# 06_-_IO_Ports.net
KiCad netlist of a schematic drawn in Altium Designer
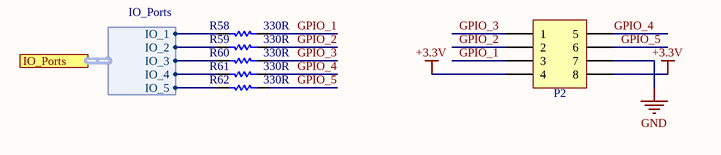
[diagram p0: [06] - IO_Ports.SchDoc]

(export (version "E")
  (design (tool "Eeschema 10.0.6"))
  (components
    (comp (ref "P2")
      (value "Header 4X2A")
      (footprint "HDR2X4_CEN")
      (description "Header, 4-Pin, Dual row")
      (fields (field (name "PUBLISHER") "Altium Limited"))
      (libsource (lib "Miscellaneous Connectors") (part "Header 4X2A"))
    )
    (comp (ref "R58")
      (value "Res1")
      (footprint "Res-0603")
      (description "Chip Resistor")
      (fields
        (field (name "MANUFACTURER") "Panasonic")
        (field (name "MANUFACTURER PART NUMBER") "ERJ-3EKF3300V")
        (field (name "RESISTANCE") "330R")
      )
      (libsource (lib "Altium_Library") (part "Res1"))
    )
    (comp (ref "R59")
      (value "Res1")
      (footprint "Res-0603")
      (description "Chip Resistor")
      (fields
        (field (name "MANUFACTURER") "Panasonic")
        (field (name "MANUFACTURER PART NUMBER") "ERJ-3EKF3300V")
        (field (name "RESISTANCE") "330R")
      )
      (libsource (lib "Altium_Library") (part "Res1"))
    )
    (comp (ref "R60")
      (value "Res1")
      (footprint "Res-0603")
      (description "Chip Resistor")
      (fields
        (field (name "MANUFACTURER") "Panasonic")
        (field (name "MANUFACTURER PART NUMBER") "ERJ-3EKF3300V")
        (field (name "RESISTANCE") "330R")
      )
      (libsource (lib "Altium_Library") (part "Res1"))
    )
    (comp (ref "R61")
      (value "Res1")
      (footprint "Res-0603")
      (description "Chip Resistor")
      (fields
        (field (name "MANUFACTURER") "Panasonic")
        (field (name "MANUFACTURER PART NUMBER") "ERJ-3EKF3300V")
        (field (name "RESISTANCE") "330R")
      )
      (libsource (lib "Altium_Library") (part "Res1"))
    )
    (comp (ref "R62")
      (value "Res1")
      (footprint "Res-0603")
      (description "Chip Resistor")
      (fields
        (field (name "MANUFACTURER") "Panasonic")
        (field (name "MANUFACTURER PART NUMBER") "ERJ-3EKF3300V")
        (field (name "RESISTANCE") "330R")
      )
      (libsource (lib "Altium_Library") (part "Res1"))
    )
  )
  (nets
    (net (code "2") (name "+3.3V") (class "Default")
      (node (ref "P2") (pin "4") (pinfunction "4_4") (pintype "passive"))
      (node (ref "P2") (pin "8") (pinfunction "8_8") (pintype "passive"))
    )
    (net (code "3") (name "/GPIO_1") (class "Default")
      (node (ref "P2") (pin "3") (pinfunction "3_3") (pintype "passive"))
      (node (ref "R58") (pin "2") (pinfunction "2_2") (pintype "passive"))
    )
    (net (code "4") (name "/GPIO_2") (class "Default")
      (node (ref "P2") (pin "2") (pinfunction "2_2") (pintype "passive"))
      (node (ref "R59") (pin "2") (pinfunction "2_2") (pintype "passive"))
    )
    (net (code "5") (name "/GPIO_3") (class "Default")
      (node (ref "P2") (pin "1") (pinfunction "1_1") (pintype "passive"))
      (node (ref "R60") (pin "2") (pinfunction "2_2") (pintype "passive"))
    )
    (net (code "6") (name "/GPIO_4") (class "Default")
      (node (ref "P2") (pin "5") (pinfunction "5_5") (pintype "passive"))
      (node (ref "R61") (pin "2") (pinfunction "2_2") (pintype "passive"))
    )
    (net (code "7") (name "/GPIO_5") (class "Default")
      (node (ref "P2") (pin "6") (pinfunction "6_6") (pintype "passive"))
      (node (ref "R62") (pin "2") (pinfunction "2_2") (pintype "passive"))
    )
    (net (code "8") (name "/IO_1") (class "Default")
      (node (ref "R58") (pin "1") (pinfunction "1_1") (pintype "passive"))
    )
    (net (code "9") (name "/IO_2") (class "Default")
      (node (ref "R59") (pin "1") (pinfunction "1_1") (pintype "passive"))
    )
    (net (code "10") (name "/IO_3") (class "Default")
      (node (ref "R60") (pin "1") (pinfunction "1_1") (pintype "passive"))
    )
    (net (code "11") (name "/IO_4") (class "Default")
      (node (ref "R61") (pin "1") (pinfunction "1_1") (pintype "passive"))
    )
    (net (code "12") (name "/IO_5") (class "Default")
      (node (ref "R62") (pin "1") (pinfunction "1_1") (pintype "passive"))
    )
    (net (code "14") (name "GND") (class "Default")
      (node (ref "P2") (pin "7") (pinfunction "7_7") (pintype "passive"))
    )
  )
)
